# USBHead.net
KiCad netlist of a schematic drawn in EasyEDA Pro
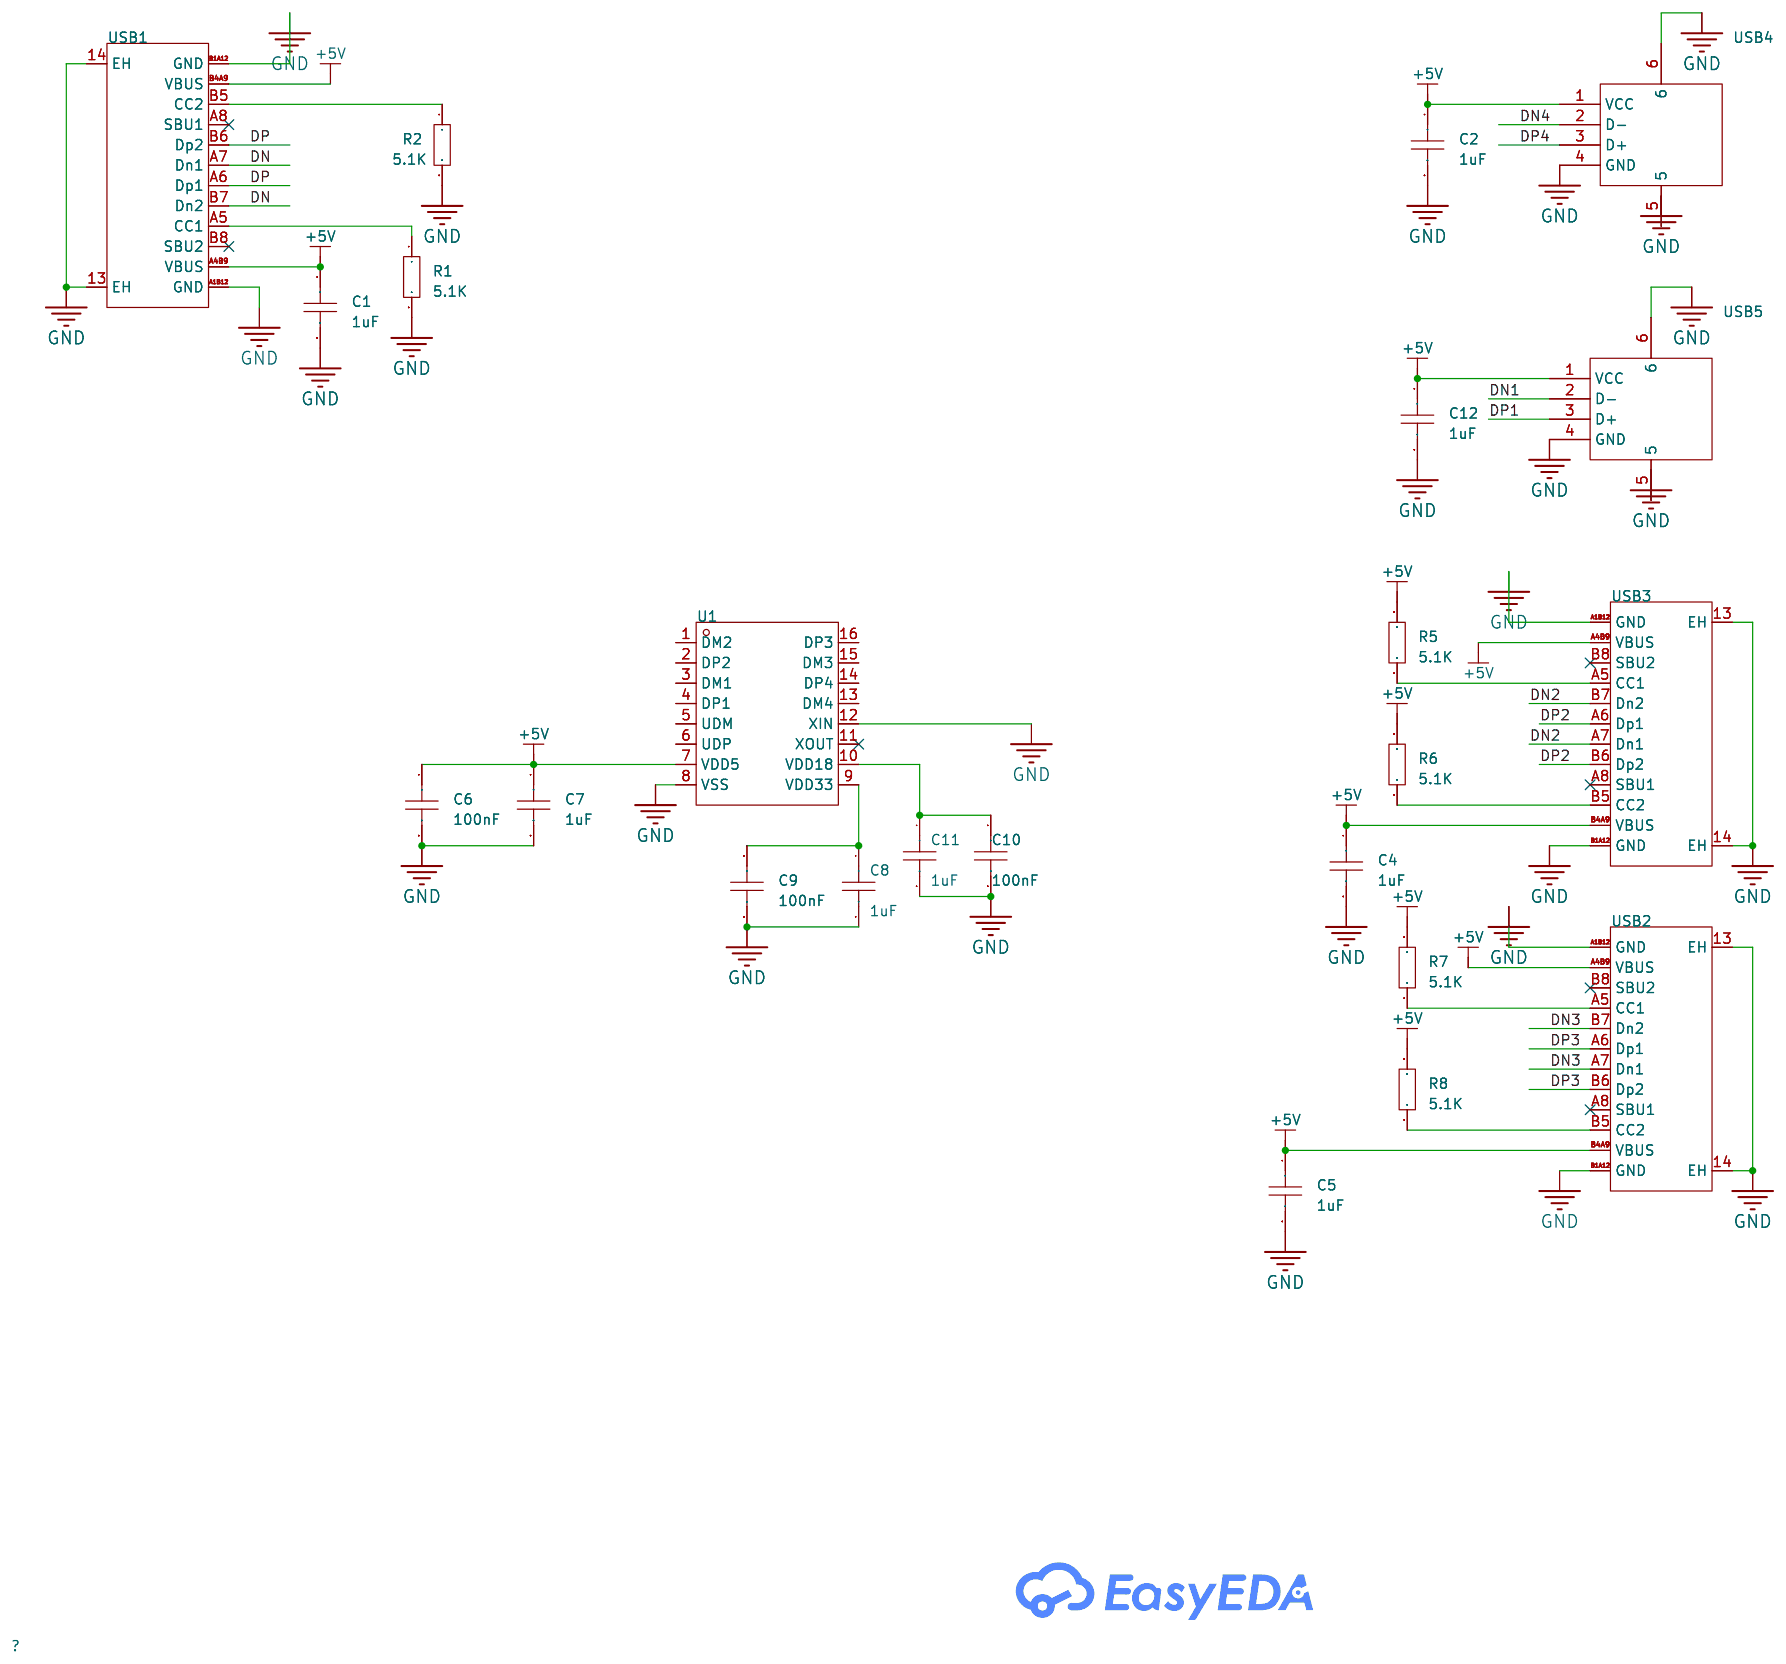
[diagram p0: schematic sheet]

(export (version "E")
  (design (tool "Eeschema 10.0.6"))
  (components
    (comp (ref "C1") (value "1uF") (footprint "easyedapro:C0603") (libsource (lib "easyedapro") (part "CAP")))
    (comp (ref "C2") (value "1uF") (footprint "easyedapro:C0603") (libsource (lib "easyedapro") (part "CAP")))
    (comp (ref "C4") (value "1uF") (footprint "easyedapro:C0603") (libsource (lib "easyedapro") (part "CAP")))
    (comp (ref "C5") (value "1uF") (footprint "easyedapro:C0603") (libsource (lib "easyedapro") (part "CAP")))
    (comp (ref "C6")
      (value "100nF")
      (footprint "easyedapro:C0603")
      (libsource (lib "easyedapro") (part "CAP"))
    )
    (comp (ref "C7") (value "1uF") (footprint "easyedapro:C0603") (libsource (lib "easyedapro") (part "CAP")))
    (comp (ref "C8") (value "1uF") (footprint "easyedapro:C0603") (libsource (lib "easyedapro") (part "CAP")))
    (comp (ref "C9")
      (value "100nF")
      (footprint "easyedapro:C0603")
      (libsource (lib "easyedapro") (part "CAP"))
    )
    (comp (ref "C10")
      (value "100nF")
      (footprint "easyedapro:C0603")
      (libsource (lib "easyedapro") (part "CAP"))
    )
    (comp (ref "C11")
      (value "1uF")
      (footprint "easyedapro:C0603")
      (libsource (lib "easyedapro") (part "CAP"))
    )
    (comp (ref "C12")
      (value "1uF")
      (footprint "easyedapro:C0603")
      (libsource (lib "easyedapro") (part "CAP"))
    )
    (comp (ref "R1")
      (value "5.1K")
      (footprint "easyedapro:R0603")
      (libsource (lib "easyedapro") (part "Res"))
    )
    (comp (ref "R2")
      (value "5.1K")
      (footprint "easyedapro:R0603")
      (libsource (lib "easyedapro") (part "Res"))
    )
    (comp (ref "R5")
      (value "5.1K")
      (footprint "easyedapro:R0603")
      (libsource (lib "easyedapro") (part "Res"))
    )
    (comp (ref "R6")
      (value "5.1K")
      (footprint "easyedapro:R0603")
      (libsource (lib "easyedapro") (part "Res"))
    )
    (comp (ref "R7")
      (value "5.1K")
      (footprint "easyedapro:R0603")
      (libsource (lib "easyedapro") (part "Res"))
    )
    (comp (ref "R8")
      (value "5.1K")
      (footprint "easyedapro:R0603")
      (libsource (lib "easyedapro") (part "Res"))
    )
    (comp (ref "U1")
      (value "SL2.1s")
      (footprint "easyedapro:SSOP-16_L4.6-W2.6-P0.53-LS4.0-BL")
      (fields (field (name "Manufacturer") "CoreChips(和芯润德)"))
      (libsource (lib "easyedapro") (part "SL2.1S"))
    )
    (comp (ref "USB1")
      (value "TYPE-C 16PIN 2MD(073)")
      (footprint "easyedapro:USB-C-SMD_TYPE-C-16PIN-2MD-073")
      (fields (field (name "Manufacturer") "SHOU HAN(首韩)"))
      (libsource (lib "easyedapro") (part "TYPE-C 16PIN 2MD(073)"))
    )
    (comp (ref "USB2")
      (value "TYPE-C 16PIN 2MD(073)")
      (footprint "easyedapro:USB-C-SMD_TYPE-C-16PIN-2MD-073")
      (fields (field (name "Manufacturer") "SHOU HAN(首韩)"))
      (libsource (lib "easyedapro") (part "TYPE-C 16PIN 2MD(073)"))
    )
    (comp (ref "USB3")
      (value "TYPE-C 16PIN 2MD(073)")
      (footprint "easyedapro:USB-C-SMD_TYPE-C-16PIN-2MD-073")
      (fields (field (name "Manufacturer") "SHOU HAN(首韩)"))
      (libsource (lib "easyedapro") (part "TYPE-C 16PIN 2MD(073)"))
    )
    (comp (ref "USB4")
      (value "10.0 QHHTZB6.3")
      (footprint "easyedapro:USB-A-TH_10.0QHHTZB6.3")
      (fields (field (name "Manufacturer") "SHOU HAN(首韩)"))
      (libsource (lib "easyedapro") (part "10.0 QHHTZB6.3"))
    )
    (comp (ref "USB5")
      (value "10.0 QHHTZB6.3")
      (footprint "easyedapro:USB-A-TH_10.0QHHTZB6.3")
      (fields (field (name "Manufacturer") "SHOU HAN(首韩)"))
      (libsource (lib "easyedapro") (part "10.0 QHHTZB6.3"))
    )
  )
  (nets
    (net (code "1") (name "+5V") (class "Default")
      (node (ref "C1") (pin "1") (pinfunction "1_1") (pintype "input"))
      (node (ref "C12") (pin "1") (pinfunction "1_1") (pintype "input"))
      (node (ref "C2") (pin "1") (pinfunction "1_1") (pintype "input"))
      (node (ref "C4") (pin "1") (pinfunction "1_1") (pintype "input"))
      (node (ref "C5") (pin "1") (pinfunction "1_1") (pintype "input"))
      (node (ref "C6") (pin "1") (pinfunction "1_1") (pintype "input"))
      (node (ref "C7") (pin "1") (pinfunction "1_1") (pintype "input"))
      (node (ref "R5") (pin "2") (pinfunction "2_2") (pintype "input"))
      (node (ref "R6") (pin "2") (pinfunction "2_2") (pintype "input"))
      (node (ref "R7") (pin "2") (pinfunction "2_2") (pintype "input"))
      (node (ref "R8") (pin "2") (pinfunction "2_2") (pintype "input"))
      (node (ref "U1") (pin "7") (pinfunction "VDD5_7") (pintype "unspecified"))
      (node (ref "USB1") (pin "A4B9") (pinfunction "VBUS_A4B9") (pintype "unspecified"))
      (node (ref "USB1") (pin "B4A9") (pinfunction "VBUS_B4A9") (pintype "unspecified"))
      (node (ref "USB2") (pin "A4B9") (pinfunction "VBUS_A4B9") (pintype "unspecified"))
      (node (ref "USB2") (pin "B4A9") (pinfunction "VBUS_B4A9") (pintype "unspecified"))
      (node (ref "USB3") (pin "A4B9") (pinfunction "VBUS_A4B9") (pintype "unspecified"))
      (node (ref "USB3") (pin "B4A9") (pinfunction "VBUS_B4A9") (pintype "unspecified"))
      (node (ref "USB4") (pin "1") (pinfunction "VCC_1") (pintype "unspecified"))
      (node (ref "USB5") (pin "1") (pinfunction "VCC_1") (pintype "unspecified"))
    )
    (net (code "2") (name "/DN") (class "Default")
      (node (ref "USB1") (pin "A7") (pinfunction "Dn1_A7") (pintype "unspecified"))
      (node (ref "USB1") (pin "B7") (pinfunction "Dn2_B7") (pintype "unspecified"))
    )
    (net (code "3") (name "/DN1") (class "Default")
      (node (ref "USB5") (pin "2") (pinfunction "D-_2") (pintype "unspecified"))
    )
    (net (code "4") (name "/DN2") (class "Default")
      (node (ref "USB3") (pin "A7") (pinfunction "Dn1_A7") (pintype "unspecified"))
      (node (ref "USB3") (pin "B7") (pinfunction "Dn2_B7") (pintype "unspecified"))
    )
    (net (code "5") (name "/DN3") (class "Default")
      (node (ref "USB2") (pin "A7") (pinfunction "Dn1_A7") (pintype "unspecified"))
      (node (ref "USB2") (pin "B7") (pinfunction "Dn2_B7") (pintype "unspecified"))
    )
    (net (code "6") (name "/DN4") (class "Default")
      (node (ref "USB4") (pin "2") (pinfunction "D-_2") (pintype "unspecified"))
    )
    (net (code "7") (name "/DP") (class "Default")
      (node (ref "USB1") (pin "A6") (pinfunction "Dp1_A6") (pintype "unspecified"))
      (node (ref "USB1") (pin "B6") (pinfunction "Dp2_B6") (pintype "unspecified"))
    )
    (net (code "8") (name "/DP1") (class "Default")
      (node (ref "USB5") (pin "3") (pinfunction "D+_3") (pintype "unspecified"))
    )
    (net (code "9") (name "/DP2") (class "Default")
      (node (ref "USB3") (pin "A6") (pinfunction "Dp1_A6") (pintype "unspecified"))
      (node (ref "USB3") (pin "B6") (pinfunction "Dp2_B6") (pintype "unspecified"))
    )
    (net (code "10") (name "/DP3") (class "Default")
      (node (ref "USB2") (pin "A6") (pinfunction "Dp1_A6") (pintype "unspecified"))
      (node (ref "USB2") (pin "B6") (pinfunction "Dp2_B6") (pintype "unspecified"))
    )
    (net (code "11") (name "/DP4") (class "Default")
      (node (ref "USB4") (pin "3") (pinfunction "D+_3") (pintype "unspecified"))
    )
    (net (code "12") (name "GND") (class "Default")
      (node (ref "C1") (pin "2") (pinfunction "2_2") (pintype "input"))
      (node (ref "C10") (pin "2") (pinfunction "2_2") (pintype "input"))
      (node (ref "C11") (pin "2") (pinfunction "2_2") (pintype "input"))
      (node (ref "C12") (pin "2") (pinfunction "2_2") (pintype "input"))
      (node (ref "C2") (pin "2") (pinfunction "2_2") (pintype "input"))
      (node (ref "C4") (pin "2") (pinfunction "2_2") (pintype "input"))
      (node (ref "C5") (pin "2") (pinfunction "2_2") (pintype "input"))
      (node (ref "C6") (pin "2") (pinfunction "2_2") (pintype "input"))
      (node (ref "C7") (pin "2") (pinfunction "2_2") (pintype "input"))
      (node (ref "C8") (pin "2") (pinfunction "2_2") (pintype "input"))
      (node (ref "C9") (pin "2") (pinfunction "2_2") (pintype "input"))
      (node (ref "R1") (pin "2") (pinfunction "2_2") (pintype "input"))
      (node (ref "R2") (pin "2") (pinfunction "2_2") (pintype "input"))
      (node (ref "U1") (pin "12") (pinfunction "XIN_12") (pintype "unspecified"))
      (node (ref "U1") (pin "8") (pinfunction "VSS_8") (pintype "unspecified"))
      (node (ref "USB1") (pin "13") (pinfunction "EH_13") (pintype "unspecified"))
      (node (ref "USB1") (pin "14") (pinfunction "EH_14") (pintype "unspecified"))
      (node (ref "USB1") (pin "A1B12") (pinfunction "GND_A1B12") (pintype "unspecified"))
      (node (ref "USB1") (pin "B1A12") (pinfunction "GND_B1A12") (pintype "unspecified"))
      (node (ref "USB2") (pin "13") (pinfunction "EH_13") (pintype "unspecified"))
      (node (ref "USB2") (pin "14") (pinfunction "EH_14") (pintype "unspecified"))
      (node (ref "USB2") (pin "A1B12") (pinfunction "GND_A1B12") (pintype "unspecified"))
      (node (ref "USB2") (pin "B1A12") (pinfunction "GND_B1A12") (pintype "unspecified"))
      (node (ref "USB3") (pin "13") (pinfunction "EH_13") (pintype "unspecified"))
      (node (ref "USB3") (pin "14") (pinfunction "EH_14") (pintype "unspecified"))
      (node (ref "USB3") (pin "A1B12") (pinfunction "GND_A1B12") (pintype "unspecified"))
      (node (ref "USB3") (pin "B1A12") (pinfunction "GND_B1A12") (pintype "unspecified"))
      (node (ref "USB4") (pin "4") (pinfunction "GND_4") (pintype "unspecified"))
      (node (ref "USB4") (pin "5") (pinfunction "5_5") (pintype "unspecified"))
      (node (ref "USB4") (pin "6") (pinfunction "6_6") (pintype "unspecified"))
      (node (ref "USB5") (pin "4") (pinfunction "GND_4") (pintype "unspecified"))
      (node (ref "USB5") (pin "5") (pinfunction "5_5") (pintype "unspecified"))
      (node (ref "USB5") (pin "6") (pinfunction "6_6") (pintype "unspecified"))
    )
    (net (code "13") (name "Net-(U1-VDD18)") (class "Default")
      (node (ref "C10") (pin "1") (pinfunction "1_1") (pintype "input"))
      (node (ref "C11") (pin "1") (pinfunction "1_1") (pintype "input"))
      (node (ref "U1") (pin "10") (pinfunction "VDD18_10") (pintype "unspecified"))
    )
    (net (code "14") (name "Net-(U1-VDD33)") (class "Default")
      (node (ref "C8") (pin "1") (pinfunction "1_1") (pintype "input"))
      (node (ref "C9") (pin "1") (pinfunction "1_1") (pintype "input"))
      (node (ref "U1") (pin "9") (pinfunction "VDD33_9") (pintype "unspecified"))
    )
    (net (code "15") (name "Net-(USB1-CC1)") (class "Default")
      (node (ref "R1") (pin "1") (pinfunction "1_1") (pintype "input"))
      (node (ref "USB1") (pin "A5") (pinfunction "CC1_A5") (pintype "unspecified"))
    )
    (net (code "16") (name "Net-(USB1-CC2)") (class "Default")
      (node (ref "R2") (pin "1") (pinfunction "1_1") (pintype "input"))
      (node (ref "USB1") (pin "B5") (pinfunction "CC2_B5") (pintype "unspecified"))
    )
    (net (code "17") (name "Net-(USB2-CC1)") (class "Default")
      (node (ref "R7") (pin "1") (pinfunction "1_1") (pintype "input"))
      (node (ref "USB2") (pin "A5") (pinfunction "CC1_A5") (pintype "unspecified"))
    )
    (net (code "18") (name "Net-(USB2-CC2)") (class "Default")
      (node (ref "R8") (pin "1") (pinfunction "1_1") (pintype "input"))
      (node (ref "USB2") (pin "B5") (pinfunction "CC2_B5") (pintype "unspecified"))
    )
    (net (code "19") (name "Net-(USB3-CC1)") (class "Default")
      (node (ref "R5") (pin "1") (pinfunction "1_1") (pintype "input"))
      (node (ref "USB3") (pin "A5") (pinfunction "CC1_A5") (pintype "unspecified"))
    )
    (net (code "20") (name "Net-(USB3-CC2)") (class "Default")
      (node (ref "R6") (pin "1") (pinfunction "1_1") (pintype "input"))
      (node (ref "USB3") (pin "B5") (pinfunction "CC2_B5") (pintype "unspecified"))
    )
    (net (code "21") (name "unconnected-(U1-DM1-Pad3)") (class "Default")
      (node (ref "U1") (pin "3") (pinfunction "DM1_3") (pintype "unspecified"))
    )
    (net (code "22") (name "unconnected-(U1-DM2-Pad1)") (class "Default")
      (node (ref "U1") (pin "1") (pinfunction "DM2_1") (pintype "unspecified"))
    )
    (net (code "23") (name "unconnected-(U1-DM3-Pad15)") (class "Default")
      (node (ref "U1") (pin "15") (pinfunction "DM3_15") (pintype "unspecified"))
    )
    (net (code "24") (name "unconnected-(U1-DM4-Pad13)") (class "Default")
      (node (ref "U1") (pin "13") (pinfunction "DM4_13") (pintype "unspecified"))
    )
    (net (code "25") (name "unconnected-(U1-DP1-Pad4)") (class "Default")
      (node (ref "U1") (pin "4") (pinfunction "DP1_4") (pintype "unspecified"))
    )
    (net (code "26") (name "unconnected-(U1-DP2-Pad2)") (class "Default")
      (node (ref "U1") (pin "2") (pinfunction "DP2_2") (pintype "unspecified"))
    )
    (net (code "27") (name "unconnected-(U1-DP3-Pad16)") (class "Default")
      (node (ref "U1") (pin "16") (pinfunction "DP3_16") (pintype "unspecified"))
    )
    (net (code "28") (name "unconnected-(U1-DP4-Pad14)") (class "Default")
      (node (ref "U1") (pin "14") (pinfunction "DP4_14") (pintype "unspecified"))
    )
    (net (code "29") (name "unconnected-(U1-UDM-Pad5)") (class "Default")
      (node (ref "U1") (pin "5") (pinfunction "UDM_5") (pintype "unspecified"))
    )
    (net (code "30") (name "unconnected-(U1-UDP-Pad6)") (class "Default")
      (node (ref "U1") (pin "6") (pinfunction "UDP_6") (pintype "unspecified"))
    )
    (net (code "31") (name "unconnected-(U1-XOUT-Pad11)") (class "Default")
      (node (ref "U1") (pin "11") (pinfunction "XOUT_11") (pintype "unspecified+no_connect"))
    )
    (net (code "32") (name "unconnected-(USB1-SBU1-PadA8)") (class "Default")
      (node (ref "USB1") (pin "A8") (pinfunction "SBU1_A8") (pintype "unspecified+no_connect"))
    )
    (net (code "33") (name "unconnected-(USB1-SBU2-PadB8)") (class "Default")
      (node (ref "USB1") (pin "B8") (pinfunction "SBU2_B8") (pintype "unspecified+no_connect"))
    )
    (net (code "34") (name "unconnected-(USB2-SBU1-PadA8)") (class "Default")
      (node (ref "USB2") (pin "A8") (pinfunction "SBU1_A8") (pintype "unspecified+no_connect"))
    )
    (net (code "35") (name "unconnected-(USB2-SBU2-PadB8)") (class "Default")
      (node (ref "USB2") (pin "B8") (pinfunction "SBU2_B8") (pintype "unspecified+no_connect"))
    )
    (net (code "36") (name "unconnected-(USB3-SBU1-PadA8)") (class "Default")
      (node (ref "USB3") (pin "A8") (pinfunction "SBU1_A8") (pintype "unspecified+no_connect"))
    )
    (net (code "37") (name "unconnected-(USB3-SBU2-PadB8)") (class "Default")
      (node (ref "USB3") (pin "B8") (pinfunction "SBU2_B8") (pintype "unspecified+no_connect"))
    )
  )
)
